# EvalBoard.net
KiCad netlist of a schematic drawn in EAGLE
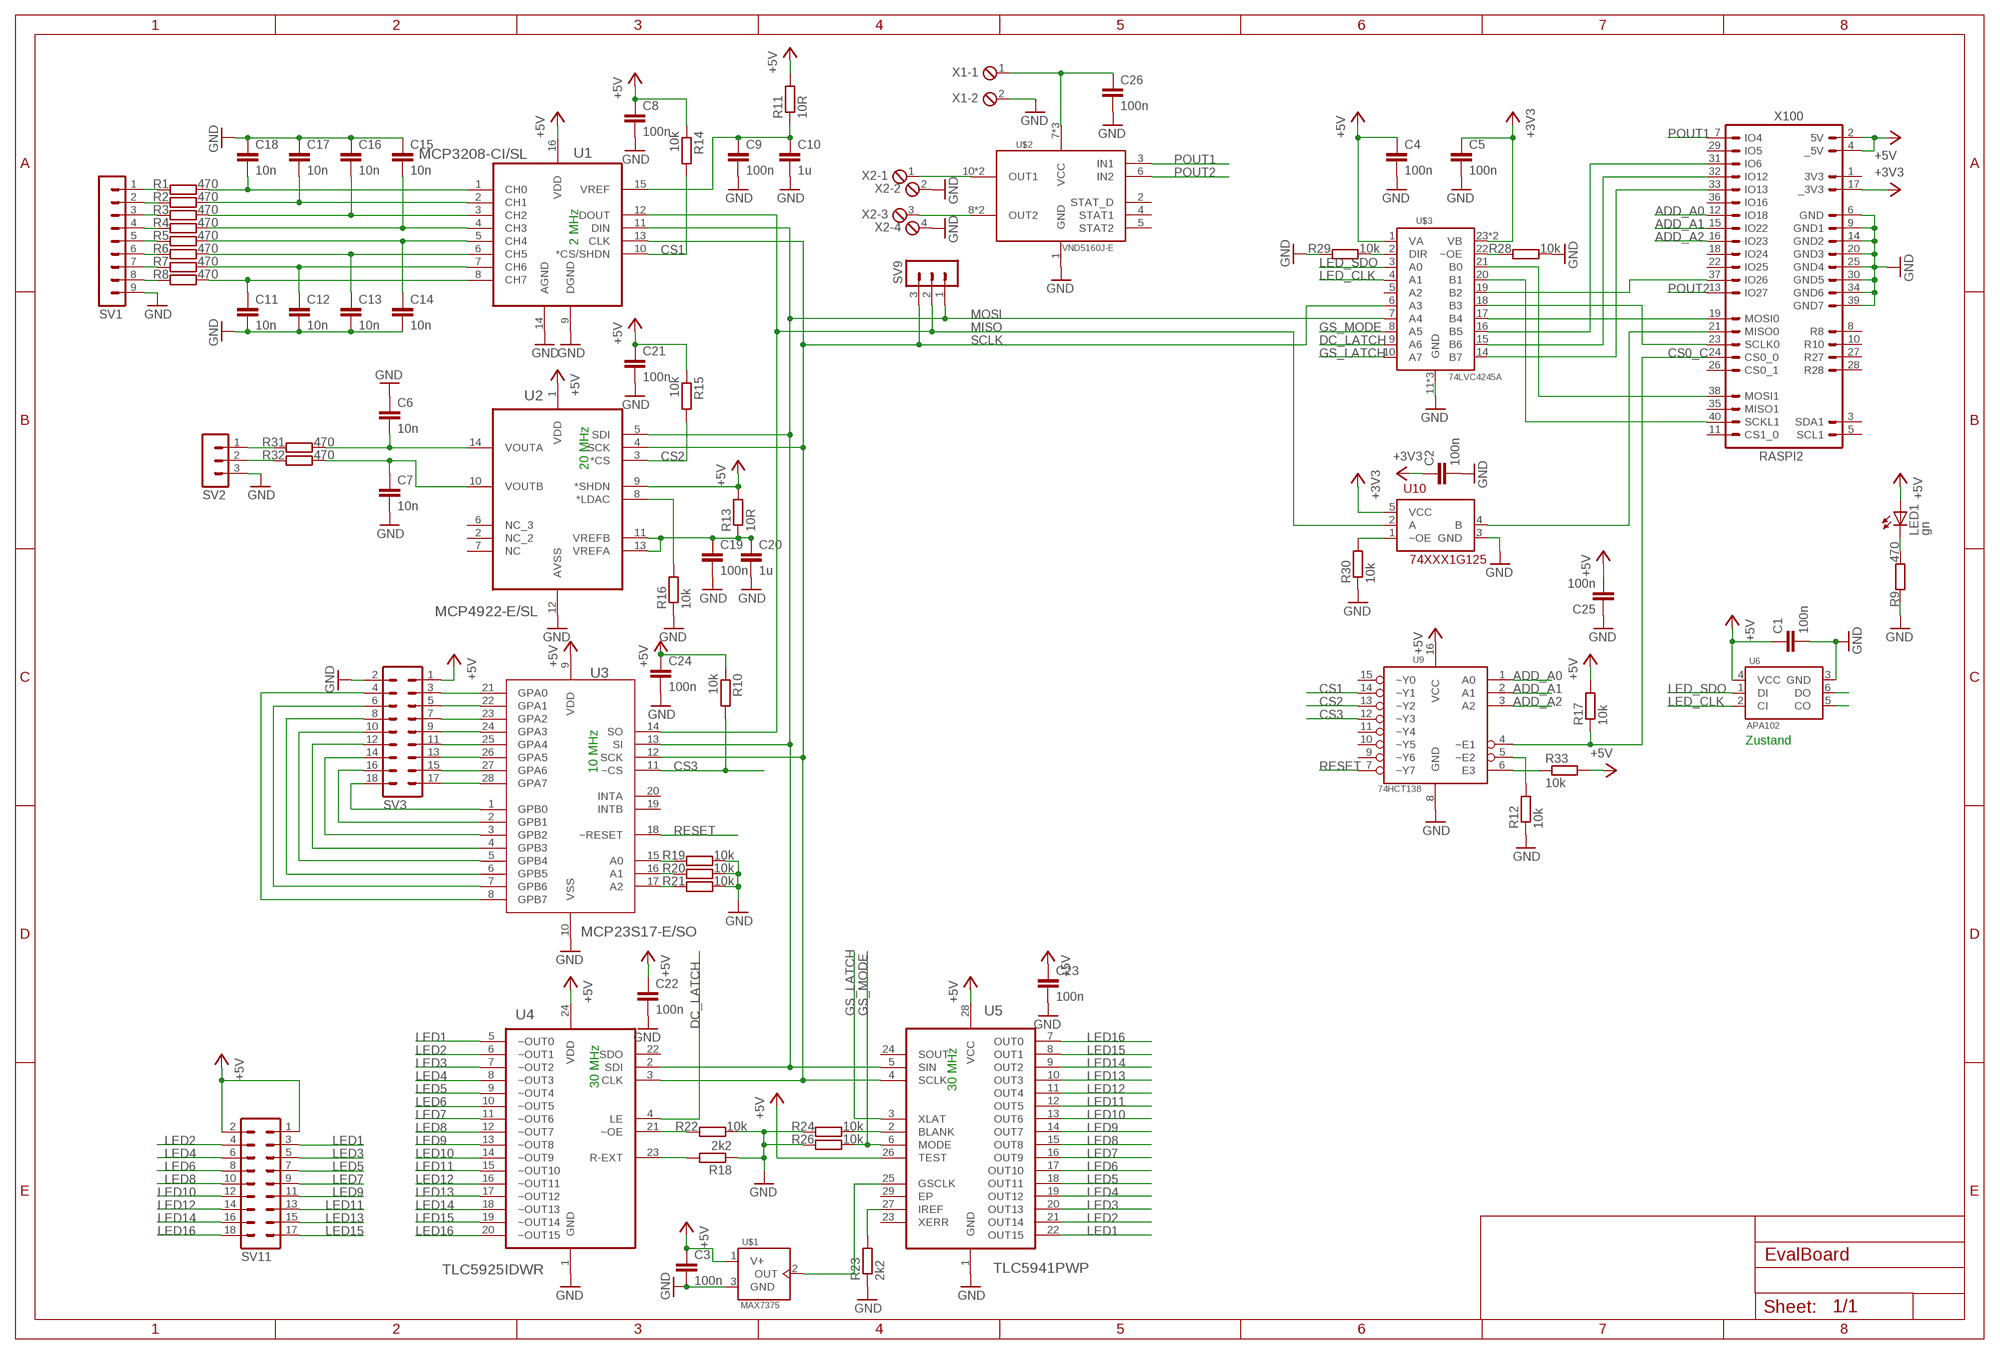
[diagram p0: schematic, sheet 1]

(export (version "E")
  (design (tool "Eeschema 10.0.6"))
  (components
    (comp (ref "C1")
      (value "100n")
      (footprint "eagle-import:C0805")
      (libsource (lib "eagle-import") (part "C-EUC0805"))
    )
    (comp (ref "C2")
      (value "100n")
      (footprint "eagle-import:C0805")
      (libsource (lib "eagle-import") (part "C-EUC0805"))
    )
    (comp (ref "C3")
      (value "100n")
      (footprint "eagle-import:C0805")
      (libsource (lib "eagle-import") (part "C-EUC0805"))
    )
    (comp (ref "C4")
      (value "100n")
      (footprint "eagle-import:C0805")
      (libsource (lib "eagle-import") (part "C-EUC0805"))
    )
    (comp (ref "C5")
      (value "100n")
      (footprint "eagle-import:C0805")
      (libsource (lib "eagle-import") (part "C-EUC0805"))
    )
    (comp (ref "C6")
      (value "10n")
      (footprint "eagle-import:C0805")
      (libsource (lib "eagle-import") (part "C-EUC0805"))
    )
    (comp (ref "C7")
      (value "10n")
      (footprint "eagle-import:C0805")
      (libsource (lib "eagle-import") (part "C-EUC0805"))
    )
    (comp (ref "C8")
      (value "100n")
      (footprint "eagle-import:C0805")
      (libsource (lib "eagle-import") (part "C-EUC0805"))
    )
    (comp (ref "C9")
      (value "100n")
      (footprint "eagle-import:C0805")
      (libsource (lib "eagle-import") (part "C-EUC0805"))
    )
    (comp (ref "C10")
      (value "1u")
      (footprint "eagle-import:C0805")
      (libsource (lib "eagle-import") (part "C-EUC0805"))
    )
    (comp (ref "C11")
      (value "10n")
      (footprint "eagle-import:C0805")
      (libsource (lib "eagle-import") (part "C-EUC0805"))
    )
    (comp (ref "C12")
      (value "10n")
      (footprint "eagle-import:C0805")
      (libsource (lib "eagle-import") (part "C-EUC0805"))
    )
    (comp (ref "C13")
      (value "10n")
      (footprint "eagle-import:C0805")
      (libsource (lib "eagle-import") (part "C-EUC0805"))
    )
    (comp (ref "C14")
      (value "10n")
      (footprint "eagle-import:C0805")
      (libsource (lib "eagle-import") (part "C-EUC0805"))
    )
    (comp (ref "C15")
      (value "10n")
      (footprint "eagle-import:C0805")
      (libsource (lib "eagle-import") (part "C-EUC0805"))
    )
    (comp (ref "C16")
      (value "10n")
      (footprint "eagle-import:C0805")
      (libsource (lib "eagle-import") (part "C-EUC0805"))
    )
    (comp (ref "C17")
      (value "10n")
      (footprint "eagle-import:C0805")
      (libsource (lib "eagle-import") (part "C-EUC0805"))
    )
    (comp (ref "C18")
      (value "10n")
      (footprint "eagle-import:C0805")
      (libsource (lib "eagle-import") (part "C-EUC0805"))
    )
    (comp (ref "C19")
      (value "100n")
      (footprint "eagle-import:C0805")
      (libsource (lib "eagle-import") (part "C-EUC0805"))
    )
    (comp (ref "C20")
      (value "1u")
      (footprint "eagle-import:C0805")
      (libsource (lib "eagle-import") (part "C-EUC0805"))
    )
    (comp (ref "C21")
      (value "100n")
      (footprint "eagle-import:C0805")
      (libsource (lib "eagle-import") (part "C-EUC0805"))
    )
    (comp (ref "C22")
      (value "100n")
      (footprint "eagle-import:C0805")
      (libsource (lib "eagle-import") (part "C-EUC0805"))
    )
    (comp (ref "C23")
      (value "100n")
      (footprint "eagle-import:C0805")
      (libsource (lib "eagle-import") (part "C-EUC0805"))
    )
    (comp (ref "C24")
      (value "100n")
      (footprint "eagle-import:C0805")
      (libsource (lib "eagle-import") (part "C-EUC0805"))
    )
    (comp (ref "C25")
      (value "100n")
      (footprint "eagle-import:C0805")
      (libsource (lib "eagle-import") (part "C-EUC0805"))
    )
    (comp (ref "C26")
      (value "100n")
      (footprint "eagle-import:C0805")
      (libsource (lib "eagle-import") (part "C-EUC0805"))
    )
    (comp (ref "LED1")
      (value "gn")
      (footprint "eagle-import:LED5MM")
      (libsource (lib "eagle-import") (part "LED5MM"))
    )
    (comp (ref "R1")
      (value "470")
      (footprint "eagle-import:R0805")
      (libsource (lib "eagle-import") (part "R-EU_R0805"))
    )
    (comp (ref "R2")
      (value "470")
      (footprint "eagle-import:R0805")
      (libsource (lib "eagle-import") (part "R-EU_R0805"))
    )
    (comp (ref "R3")
      (value "470")
      (footprint "eagle-import:R0805")
      (libsource (lib "eagle-import") (part "R-EU_R0805"))
    )
    (comp (ref "R4")
      (value "470")
      (footprint "eagle-import:R0805")
      (libsource (lib "eagle-import") (part "R-EU_R0805"))
    )
    (comp (ref "R5")
      (value "470")
      (footprint "eagle-import:R0805")
      (libsource (lib "eagle-import") (part "R-EU_R0805"))
    )
    (comp (ref "R6")
      (value "470")
      (footprint "eagle-import:R0805")
      (libsource (lib "eagle-import") (part "R-EU_R0805"))
    )
    (comp (ref "R7")
      (value "470")
      (footprint "eagle-import:R0805")
      (libsource (lib "eagle-import") (part "R-EU_R0805"))
    )
    (comp (ref "R8")
      (value "470")
      (footprint "eagle-import:R0805")
      (libsource (lib "eagle-import") (part "R-EU_R0805"))
    )
    (comp (ref "R9")
      (value "470")
      (footprint "eagle-import:R0805")
      (libsource (lib "eagle-import") (part "R-EU_R0805"))
    )
    (comp (ref "R10")
      (value "10k")
      (footprint "eagle-import:R0805")
      (libsource (lib "eagle-import") (part "R-EU_R0805"))
    )
    (comp (ref "R11")
      (value "10R")
      (footprint "eagle-import:R0805")
      (libsource (lib "eagle-import") (part "R-EU_R0805"))
    )
    (comp (ref "R12")
      (value "10k")
      (footprint "eagle-import:R0805")
      (libsource (lib "eagle-import") (part "R-EU_R0805"))
    )
    (comp (ref "R13")
      (value "10R")
      (footprint "eagle-import:R0805")
      (libsource (lib "eagle-import") (part "R-EU_R0805"))
    )
    (comp (ref "R14")
      (value "10k")
      (footprint "eagle-import:R0805")
      (libsource (lib "eagle-import") (part "R-EU_R0805"))
    )
    (comp (ref "R15")
      (value "10k")
      (footprint "eagle-import:R0805")
      (libsource (lib "eagle-import") (part "R-EU_R0805"))
    )
    (comp (ref "R16")
      (value "10k")
      (footprint "eagle-import:R0805")
      (libsource (lib "eagle-import") (part "R-EU_R0805"))
    )
    (comp (ref "R17")
      (value "10k")
      (footprint "eagle-import:R0805")
      (libsource (lib "eagle-import") (part "R-EU_R0805"))
    )
    (comp (ref "R18")
      (value "2k2")
      (footprint "eagle-import:R0805")
      (libsource (lib "eagle-import") (part "R-EU_R0805"))
    )
    (comp (ref "R19")
      (value "10k")
      (footprint "eagle-import:R0805")
      (libsource (lib "eagle-import") (part "R-EU_R0805"))
    )
    (comp (ref "R20")
      (value "10k")
      (footprint "eagle-import:R0805")
      (libsource (lib "eagle-import") (part "R-EU_R0805"))
    )
    (comp (ref "R21")
      (value "10k")
      (footprint "eagle-import:R0805")
      (libsource (lib "eagle-import") (part "R-EU_R0805"))
    )
    (comp (ref "R22")
      (value "10k")
      (footprint "eagle-import:R0805")
      (libsource (lib "eagle-import") (part "R-EU_R0805"))
    )
    (comp (ref "R23")
      (value "2k2")
      (footprint "eagle-import:R0805")
      (libsource (lib "eagle-import") (part "R-EU_R0805"))
    )
    (comp (ref "R24")
      (value "10k")
      (footprint "eagle-import:R0805")
      (libsource (lib "eagle-import") (part "R-EU_R0805"))
    )
    (comp (ref "R26")
      (value "10k")
      (footprint "eagle-import:R0805")
      (libsource (lib "eagle-import") (part "R-EU_R0805"))
    )
    (comp (ref "R28")
      (value "10k")
      (footprint "eagle-import:R0805")
      (libsource (lib "eagle-import") (part "R-EU_R0805"))
    )
    (comp (ref "R29")
      (value "10k")
      (footprint "eagle-import:R0805")
      (libsource (lib "eagle-import") (part "R-EU_R0805"))
    )
    (comp (ref "R30")
      (value "10k")
      (footprint "eagle-import:R0805")
      (libsource (lib "eagle-import") (part "R-EU_R0805"))
    )
    (comp (ref "R31")
      (value "470")
      (footprint "eagle-import:R0805")
      (libsource (lib "eagle-import") (part "R-EU_R0805"))
    )
    (comp (ref "R32")
      (value "470")
      (footprint "eagle-import:R0805")
      (libsource (lib "eagle-import") (part "R-EU_R0805"))
    )
    (comp (ref "R33")
      (value "10k")
      (footprint "eagle-import:R0805")
      (libsource (lib "eagle-import") (part "R-EU_R0805"))
    )
    (comp (ref "SV1")
      (value "MA09-1W")
      (footprint "eagle-import:MA09-1W")
      (libsource (lib "eagle-import") (part "MA09-1W"))
    )
    (comp (ref "SV2")
      (value "MA03-1")
      (footprint "eagle-import:MA03-1")
      (libsource (lib "eagle-import") (part "MA03-1"))
    )
    (comp (ref "SV3")
      (value "MA09-2W")
      (footprint "eagle-import:MA09-2W")
      (libsource (lib "eagle-import") (part "MA09-2W"))
    )
    (comp (ref "SV9")
      (value "MA03-1")
      (footprint "eagle-import:MA03-1")
      (libsource (lib "eagle-import") (part "MA03-1"))
    )
    (comp (ref "SV11")
      (value "MA09-2W")
      (footprint "eagle-import:MA09-2W")
      (libsource (lib "eagle-import") (part "MA09-2W"))
    )
    (comp (ref "U$1")
      (value "MAX7375")
      (footprint "eagle-import:SC70")
      (libsource (lib "eagle-import") (part "MAX7375"))
    )
    (comp (ref "U$2")
      (value "VND5160J-E")
      (footprint "eagle-import:POWERSSO12")
      (libsource (lib "eagle-import") (part "VND5160J-E"))
    )
    (comp (ref "U$3")
      (value "74LVC4245A")
      (footprint "eagle-import:SOIC127P1030X265-24N")
      (libsource (lib "eagle-import") (part "74LVC4245A"))
    )
    (comp (ref "U1")
      (value "MCP3208-CI/SL")
      (footprint "eagle-import:SOIC127P600X175-16N")
      (libsource (lib "eagle-import") (part "MCP3208-CI/SL"))
    )
    (comp (ref "U2")
      (value "MCP4922-E/SL")
      (footprint "eagle-import:SOIC127P600X175-14N")
      (libsource (lib "eagle-import") (part "MCP4922-E/SL"))
    )
    (comp (ref "U3")
      (value "MCP23S17-E/SO")
      (footprint "eagle-import:SOIC127P030X265-28N")
      (libsource (lib "eagle-import") (part "MCP23S17-E/SO"))
    )
    (comp (ref "U4")
      (value "TLC5925IDWR")
      (footprint "eagle-import:SOIC127P1030X265-24N")
      (libsource (lib "eagle-import") (part "TLC5925IDWR"))
    )
    (comp (ref "U5")
      (value "TLC5941PWP")
      (footprint "eagle-import:SOP65P640X120-29N")
      (libsource (lib "eagle-import") (part "TLC5941PWP"))
    )
    (comp (ref "U6")
      (value "APA102")
      (footprint "eagle-import:LED5050PACK")
      (libsource (lib "eagle-import") (part "APA102"))
    )
    (comp (ref "U9")
      (value "74HCT138")
      (footprint "eagle-import:SOIC127P600X175-16N")
      (libsource (lib "eagle-import") (part "74HCT138"))
    )
    (comp (ref "U10")
      (value "74XXX1G125")
      (footprint "eagle-import:SOT23-5L")
      (libsource (lib "eagle-import") (part "74XXX1G125"))
    )
    (comp (ref "X1")
      (value "MPT2")
      (footprint "eagle-import:2POL254")
      (libsource (lib "eagle-import") (part "MPT2"))
    )
    (comp (ref "X2")
      (value "MPT4")
      (footprint "eagle-import:4POL254")
      (libsource (lib "eagle-import") (part "MPT4"))
    )
    (comp (ref "X100")
      (value "RASPI2")
      (footprint "eagle-import:ML40")
      (libsource (lib "eagle-import") (part "RASPI2"))
    )
  )
  (nets
    (net (code "1") (name "+3V3") (class "Default")
      (node (ref "C2") (pin "1") (pinfunction "1_1") (pintype "passive"))
      (node (ref "C5") (pin "1") (pinfunction "1_1") (pintype "passive"))
      (node (ref "U$3") (pin "23") (pinfunction "VB_23") (pintype "power_in"))
      (node (ref "U$3") (pin "24") (pinfunction "VB_24") (pintype "power_in"))
      (node (ref "U10") (pin "5") (pinfunction "VCC_5") (pintype "bidirectional"))
      (node (ref "X100") (pin "17") (pinfunction "_3V3_17") (pintype "passive"))
    )
    (net (code "2") (name "+5V") (class "Default")
      (node (ref "C1") (pin "1") (pinfunction "1_1") (pintype "passive"))
      (node (ref "C21") (pin "1") (pinfunction "1_1") (pintype "passive"))
      (node (ref "C22") (pin "1") (pinfunction "1_1") (pintype "passive"))
      (node (ref "C23") (pin "1") (pinfunction "1_1") (pintype "passive"))
      (node (ref "C24") (pin "1") (pinfunction "1_1") (pintype "passive"))
      (node (ref "C25") (pin "2") (pinfunction "2_2") (pintype "passive"))
      (node (ref "C3") (pin "1") (pinfunction "1_1") (pintype "passive"))
      (node (ref "C4") (pin "1") (pinfunction "1_1") (pintype "passive"))
      (node (ref "C8") (pin "1") (pinfunction "1_1") (pintype "passive"))
      (node (ref "LED1") (pin "A") (pinfunction "A_A") (pintype "passive"))
      (node (ref "R10") (pin "1") (pinfunction "1_1") (pintype "passive"))
      (node (ref "R11") (pin "2") (pinfunction "2_2") (pintype "passive"))
      (node (ref "R13") (pin "2") (pinfunction "2_2") (pintype "passive"))
      (node (ref "R14") (pin "1") (pinfunction "1_1") (pintype "passive"))
      (node (ref "R15") (pin "1") (pinfunction "1_1") (pintype "passive"))
      (node (ref "R17") (pin "2") (pinfunction "2_2") (pintype "passive"))
      (node (ref "R33") (pin "2") (pinfunction "2_2") (pintype "passive"))
      (node (ref "SV11") (pin "1") (pinfunction "1_1") (pintype "passive"))
      (node (ref "SV11") (pin "2") (pinfunction "2_2") (pintype "passive"))
      (node (ref "SV3") (pin "1") (pinfunction "1_1") (pintype "passive"))
      (node (ref "U$1") (pin "1") (pinfunction "V+_1") (pintype "power_in"))
      (node (ref "U$3") (pin "1") (pinfunction "VA_1") (pintype "power_in"))
      (node (ref "U1") (pin "16") (pinfunction "VDD_16") (pintype "power_in"))
      (node (ref "U2") (pin "1") (pinfunction "VDD_1") (pintype "power_in"))
      (node (ref "U2") (pin "9") (pinfunction "*SHDN_9") (pintype "input"))
      (node (ref "U3") (pin "9") (pinfunction "VDD_9") (pintype "power_in"))
      (node (ref "U4") (pin "24") (pinfunction "VDD_24") (pintype "power_in"))
      (node (ref "U5") (pin "26") (pinfunction "TEST_26") (pintype "input"))
      (node (ref "U5") (pin "28") (pinfunction "VCC_28") (pintype "power_in"))
      (node (ref "U6") (pin "4") (pinfunction "VCC_4") (pintype "bidirectional"))
      (node (ref "U9") (pin "16") (pinfunction "VCC_16") (pintype "bidirectional"))
      (node (ref "X100") (pin "2") (pinfunction "5V_2") (pintype "passive"))
      (node (ref "X100") (pin "4") (pinfunction "_5V_4") (pintype "passive"))
    )
    (net (code "3") (name "/ADD_A0") (class "Default")
      (node (ref "U9") (pin "1") (pinfunction "A0_1") (pintype "bidirectional"))
      (node (ref "X100") (pin "12") (pinfunction "IO18_12") (pintype "passive"))
    )
    (net (code "4") (name "/ADD_A1") (class "Default")
      (node (ref "U9") (pin "2") (pinfunction "A1_2") (pintype "bidirectional"))
      (node (ref "X100") (pin "15") (pinfunction "IO22_15") (pintype "passive"))
    )
    (net (code "5") (name "/ADD_A2") (class "Default")
      (node (ref "U9") (pin "3") (pinfunction "A2_3") (pintype "bidirectional"))
      (node (ref "X100") (pin "16") (pinfunction "IO23_16") (pintype "passive"))
    )
    (net (code "6") (name "/CS0_C") (class "Default")
      (node (ref "R17") (pin "1") (pinfunction "1_1") (pintype "passive"))
      (node (ref "U9") (pin "4") (pinfunction "~{E1}_4") (pintype "bidirectional"))
      (node (ref "X100") (pin "24") (pinfunction "CS0_0_24") (pintype "passive"))
    )
    (net (code "7") (name "/CS1") (class "Default")
      (node (ref "R14") (pin "2") (pinfunction "2_2") (pintype "passive"))
      (node (ref "U1") (pin "10") (pinfunction "*CS/SHDN_10") (pintype "input"))
      (node (ref "U9") (pin "14") (pinfunction "~{Y1}_14") (pintype "bidirectional"))
    )
    (net (code "8") (name "/CS2") (class "Default")
      (node (ref "R15") (pin "2") (pinfunction "2_2") (pintype "passive"))
      (node (ref "U2") (pin "3") (pinfunction "*CS_3") (pintype "input"))
      (node (ref "U9") (pin "13") (pinfunction "~{Y2}_13") (pintype "bidirectional"))
    )
    (net (code "9") (name "/CS3") (class "Default")
      (node (ref "R10") (pin "2") (pinfunction "2_2") (pintype "passive"))
      (node (ref "U3") (pin "11") (pinfunction "~{CS}_11") (pintype "input"))
      (node (ref "U9") (pin "12") (pinfunction "~{Y3}_12") (pintype "bidirectional"))
    )
    (net (code "10") (name "/DC_LATCH") (class "Default")
      (node (ref "U$3") (pin "9") (pinfunction "A6_9") (pintype "bidirectional"))
      (node (ref "U4") (pin "4") (pinfunction "LE_4") (pintype "input"))
    )
    (net (code "11") (name "/GS_LATCH") (class "Default")
      (node (ref "U$3") (pin "10") (pinfunction "A7_10") (pintype "bidirectional"))
      (node (ref "U5") (pin "3") (pinfunction "XLAT_3") (pintype "input"))
    )
    (net (code "12") (name "/GS_MODE") (class "Default")
      (node (ref "R26") (pin "2") (pinfunction "2_2") (pintype "passive"))
      (node (ref "U$3") (pin "8") (pinfunction "A5_8") (pintype "bidirectional"))
      (node (ref "U5") (pin "6") (pinfunction "MODE_6") (pintype "input"))
    )
    (net (code "13") (name "/LED1") (class "Default")
      (node (ref "SV11") (pin "3") (pinfunction "3_3") (pintype "passive"))
      (node (ref "U4") (pin "5") (pinfunction "~{OUT0}_5") (pintype "output"))
      (node (ref "U5") (pin "22") (pinfunction "OUT15_22") (pintype "output"))
    )
    (net (code "14") (name "/LED2") (class "Default")
      (node (ref "SV11") (pin "4") (pinfunction "4_4") (pintype "passive"))
      (node (ref "U4") (pin "6") (pinfunction "~{OUT1}_6") (pintype "output"))
      (node (ref "U5") (pin "21") (pinfunction "OUT14_21") (pintype "output"))
    )
    (net (code "15") (name "/LED3") (class "Default")
      (node (ref "SV11") (pin "5") (pinfunction "5_5") (pintype "passive"))
      (node (ref "U4") (pin "7") (pinfunction "~{OUT2}_7") (pintype "output"))
      (node (ref "U5") (pin "20") (pinfunction "OUT13_20") (pintype "output"))
    )
    (net (code "16") (name "/LED4") (class "Default")
      (node (ref "SV11") (pin "6") (pinfunction "6_6") (pintype "passive"))
      (node (ref "U4") (pin "8") (pinfunction "~{OUT3}_8") (pintype "output"))
      (node (ref "U5") (pin "19") (pinfunction "OUT12_19") (pintype "output"))
    )
    (net (code "17") (name "/LED5") (class "Default")
      (node (ref "SV11") (pin "7") (pinfunction "7_7") (pintype "passive"))
      (node (ref "U4") (pin "9") (pinfunction "~{OUT4}_9") (pintype "output"))
      (node (ref "U5") (pin "18") (pinfunction "OUT11_18") (pintype "output"))
    )
    (net (code "18") (name "/LED6") (class "Default")
      (node (ref "SV11") (pin "8") (pinfunction "8_8") (pintype "passive"))
      (node (ref "U4") (pin "10") (pinfunction "~{OUT5}_10") (pintype "output"))
      (node (ref "U5") (pin "17") (pinfunction "OUT10_17") (pintype "output"))
    )
    (net (code "19") (name "/LED7") (class "Default")
      (node (ref "SV11") (pin "9") (pinfunction "9_9") (pintype "passive"))
      (node (ref "U4") (pin "11") (pinfunction "~{OUT6}_11") (pintype "output"))
      (node (ref "U5") (pin "16") (pinfunction "OUT9_16") (pintype "output"))
    )
    (net (code "20") (name "/LED8") (class "Default")
      (node (ref "SV11") (pin "10") (pinfunction "10_10") (pintype "passive"))
      (node (ref "U4") (pin "12") (pinfunction "~{OUT7}_12") (pintype "output"))
      (node (ref "U5") (pin "15") (pinfunction "OUT8_15") (pintype "output"))
    )
    (net (code "21") (name "/LED9") (class "Default")
      (node (ref "SV11") (pin "11") (pinfunction "11_11") (pintype "passive"))
      (node (ref "U4") (pin "13") (pinfunction "~{OUT8}_13") (pintype "output"))
      (node (ref "U5") (pin "14") (pinfunction "OUT7_14") (pintype "output"))
    )
    (net (code "22") (name "/LED10") (class "Default")
      (node (ref "SV11") (pin "12") (pinfunction "12_12") (pintype "passive"))
      (node (ref "U4") (pin "14") (pinfunction "~{OUT9}_14") (pintype "output"))
      (node (ref "U5") (pin "13") (pinfunction "OUT6_13") (pintype "output"))
    )
    (net (code "23") (name "/LED11") (class "Default")
      (node (ref "SV11") (pin "13") (pinfunction "13_13") (pintype "passive"))
      (node (ref "U4") (pin "15") (pinfunction "~{OUT10}_15") (pintype "output"))
      (node (ref "U5") (pin "12") (pinfunction "OUT5_12") (pintype "output"))
    )
    (net (code "24") (name "/LED12") (class "Default")
      (node (ref "SV11") (pin "14") (pinfunction "14_14") (pintype "passive"))
      (node (ref "U4") (pin "16") (pinfunction "~{OUT11}_16") (pintype "output"))
      (node (ref "U5") (pin "11") (pinfunction "OUT4_11") (pintype "output"))
    )
    (net (code "25") (name "/LED13") (class "Default")
      (node (ref "SV11") (pin "15") (pinfunction "15_15") (pintype "passive"))
      (node (ref "U4") (pin "17") (pinfunction "~{OUT12}_17") (pintype "output"))
      (node (ref "U5") (pin "10") (pinfunction "OUT3_10") (pintype "output"))
    )
    (net (code "26") (name "/LED14") (class "Default")
      (node (ref "SV11") (pin "16") (pinfunction "16_16") (pintype "passive"))
      (node (ref "U4") (pin "18") (pinfunction "~{OUT13}_18") (pintype "output"))
      (node (ref "U5") (pin "9") (pinfunction "OUT2_9") (pintype "output"))
    )
    (net (code "27") (name "/LED15") (class "Default")
      (node (ref "SV11") (pin "17") (pinfunction "17_17") (pintype "passive"))
      (node (ref "U4") (pin "19") (pinfunction "~{OUT14}_19") (pintype "output"))
      (node (ref "U5") (pin "8") (pinfunction "OUT1_8") (pintype "output"))
    )
    (net (code "28") (name "/LED16") (class "Default")
      (node (ref "SV11") (pin "18") (pinfunction "18_18") (pintype "passive"))
      (node (ref "U4") (pin "20") (pinfunction "~{OUT15}_20") (pintype "output"))
      (node (ref "U5") (pin "7") (pinfunction "OUT0_7") (pintype "output"))
    )
    (net (code "29") (name "/LED_CLK") (class "Default")
      (node (ref "U$3") (pin "4") (pinfunction "A1_4") (pintype "bidirectional"))
      (node (ref "U6") (pin "2") (pinfunction "CI_2") (pintype "bidirectional"))
    )
    (net (code "30") (name "/LED_SDO") (class "Default")
      (node (ref "U$3") (pin "3") (pinfunction "A0_3") (pintype "bidirectional"))
      (node (ref "U6") (pin "1") (pinfunction "DI_1") (pintype "bidirectional"))
    )
    (net (code "31") (name "/MISO") (class "Default")
      (node (ref "SV9") (pin "2") (pinfunction "2_2") (pintype "passive"))
      (node (ref "U1") (pin "12") (pinfunction "DOUT_12") (pintype "output"))
      (node (ref "U10") (pin "2") (pinfunction "A_2") (pintype "bidirectional"))
      (node (ref "U3") (pin "14") (pinfunction "SO_14") (pintype "output"))
    )
    (net (code "32") (name "/MOSI") (class "Default")
      (node (ref "SV9") (pin "1") (pinfunction "1_1") (pintype "passive"))
      (node (ref "U$3") (pin "7") (pinfunction "A4_7") (pintype "bidirectional"))
      (node (ref "U1") (pin "11") (pinfunction "DIN_11") (pintype "input"))
      (node (ref "U2") (pin "5") (pinfunction "SDI_5") (pintype "input"))
      (node (ref "U3") (pin "13") (pinfunction "SI_13") (pintype "input"))
      (node (ref "U4") (pin "2") (pinfunction "SDI_2") (pintype "input"))
      (node (ref "U5") (pin "5") (pinfunction "SIN_5") (pintype "input"))
    )
    (net (code "33") (name "/POUT1") (class "Default")
      (node (ref "U$2") (pin "3") (pinfunction "IN1_3") (pintype "input"))
      (node (ref "X100") (pin "7") (pinfunction "IO4_7") (pintype "passive"))
    )
    (net (code "34") (name "/POUT2") (class "Default")
      (node (ref "U$2") (pin "6") (pinfunction "IN2_6") (pintype "input"))
      (node (ref "X100") (pin "13") (pinfunction "IO27_13") (pintype "passive"))
    )
    (net (code "35") (name "/RESET") (class "Default")
      (node (ref "U3") (pin "18") (pinfunction "~{RESET}_18") (pintype "input"))
      (node (ref "U9") (pin "7") (pinfunction "~{Y7}_7") (pintype "bidirectional"))
    )
    (net (code "36") (name "/SCLK") (class "Default")
      (node (ref "SV9") (pin "3") (pinfunction "3_3") (pintype "passive"))
      (node (ref "U$3") (pin "6") (pinfunction "A3_6") (pintype "bidirectional"))
      (node (ref "U1") (pin "13") (pinfunction "CLK_13") (pintype "input"))
      (node (ref "U2") (pin "4") (pinfunction "SCK_4") (pintype "input"))
      (node (ref "U3") (pin "12") (pinfunction "SCK_12") (pintype "input"))
      (node (ref "U4") (pin "3") (pinfunction "CLK_3") (pintype "input"))
      (node (ref "U5") (pin "4") (pinfunction "SCLK_4") (pintype "input"))
    )
    (net (code "37") (name "GND") (class "Default")
      (node (ref "C1") (pin "2") (pinfunction "2_2") (pintype "passive"))
      (node (ref "C10") (pin "2") (pinfunction "2_2") (pintype "passive"))
      (node (ref "C11") (pin "2") (pinfunction "2_2") (pintype "passive"))
      (node (ref "C12") (pin "2") (pinfunction "2_2") (pintype "passive"))
      (node (ref "C13") (pin "2") (pinfunction "2_2") (pintype "passive"))
      (node (ref "C14") (pin "2") (pinfunction "2_2") (pintype "passive"))
      (node (ref "C15") (pin "1") (pinfunction "1_1") (pintype "passive"))
      (node (ref "C16") (pin "1") (pinfunction "1_1") (pintype "passive"))
      (node (ref "C17") (pin "1") (pinfunction "1_1") (pintype "passive"))
      (node (ref "C18") (pin "1") (pinfunction "1_1") (pintype "passive"))
      (node (ref "C19") (pin "2") (pinfunction "2_2") (pintype "passive"))
      (node (ref "C2") (pin "2") (pinfunction "2_2") (pintype "passive"))
      (node (ref "C20") (pin "2") (pinfunction "2_2") (pintype "passive"))
      (node (ref "C21") (pin "2") (pinfunction "2_2") (pintype "passive"))
      (node (ref "C22") (pin "2") (pinfunction "2_2") (pintype "passive"))
      (node (ref "C23") (pin "2") (pinfunction "2_2") (pintype "passive"))
      (node (ref "C24") (pin "2") (pinfunction "2_2") (pintype "passive"))
      (node (ref "C25") (pin "1") (pinfunction "1_1") (pintype "passive"))
      (node (ref "C26") (pin "2") (pinfunction "2_2") (pintype "passive"))
      (node (ref "C3") (pin "2") (pinfunction "2_2") (pintype "passive"))
      (node (ref "C4") (pin "2") (pinfunction "2_2") (pintype "passive"))
      (node (ref "C5") (pin "2") (pinfunction "2_2") (pintype "passive"))
      (node (ref "C6") (pin "1") (pinfunction "1_1") (pintype "passive"))
      (node (ref "C7") (pin "2") (pinfunction "2_2") (pintype "passive"))
      (node (ref "C8") (pin "2") (pinfunction "2_2") (pintype "passive"))
      (node (ref "C9") (pin "2") (pinfunction "2_2") (pintype "passive"))
      (node (ref "R12") (pin "1") (pinfunction "1_1") (pintype "passive"))
      (node (ref "R16") (pin "1") (pinfunction "1_1") (pintype "passive"))
      (node (ref "R18") (pin "1") (pinfunction "1_1") (pintype "passive"))
      (node (ref "R19") (pin "2") (pinfunction "2_2") (pintype "passive"))
      (node (ref "R20") (pin "2") (pinfunction "2_2") (pintype "passive"))
      (node (ref "R21") (pin "2") (pinfunction "2_2") (pintype "passive"))
      (node (ref "R22") (pin "2") (pinfunction "2_2") (pintype "passive"))
      (node (ref "R23") (pin "1") (pinfunction "1_1") (pintype "passive"))
      (node (ref "R24") (pin "1") (pinfunction "1_1") (pintype "passive"))
      (node (ref "R26") (pin "1") (pinfunction "1_1") (pintype "passive"))
      (node (ref "R28") (pin "2") (pinfunction "2_2") (pintype "passive"))
      (node (ref "R29") (pin "1") (pinfunction "1_1") (pintype "passive"))
      (node (ref "R30") (pin "1") (pinfunction "1_1") (pintype "passive"))
      (node (ref "R9") (pin "1") (pinfunction "1_1") (pintype "passive"))
      (node (ref "SV1") (pin "9") (pinfunction "9_9") (pintype "passive"))
      (node (ref "SV2") (pin "3") (pinfunction "3_3") (pintype "passive"))
      (node (ref "SV3") (pin "2") (pinfunction "2_2") (pintype "passive"))
      (node (ref "U$1") (pin "3") (pinfunction "GND_3") (pintype "power_in"))
      (node (ref "U$2") (pin "1") (pinfunction "GND_1") (pintype "power_in"))
      (node (ref "U$3") (pin "11") (pinfunction "GND_11") (pintype "power_in"))
      (node (ref "U$3") (pin "12") (pinfunction "GND_12") (pintype "power_in"))
      (node (ref "U$3") (pin "13") (pinfunction "GND_13") (pintype "power_in"))
      (node (ref "U1") (pin "14") (pinfunction "AGND_14") (pintype "passive"))
      (node (ref "U1") (pin "9") (pinfunction "DGND_9") (pintype "passive"))
      (node (ref "U10") (pin "3") (pinfunction "GND_3") (pintype "bidirectional"))
      (node (ref "U2") (pin "12") (pinfunction "AVSS_12") (pintype "passive"))
      (node (ref "U3") (pin "10") (pinfunction "VSS_10") (pintype "power_in"))
      (node (ref "U4") (pin "1") (pinfunction "GND_1") (pintype "passive"))
      (node (ref "U5") (pin "1") (pinfunction "GND_1") (pintype "passive"))
      (node (ref "U6") (pin "3") (pinfunction "GND_3") (pintype "bidirectional"))
      (node (ref "U9") (pin "8") (pinfunction "GND_8") (pintype "bidirectional"))
      (node (ref "X1") (pin "2") (pinfunction "1_2") (pintype "passive"))
      (node (ref "X100") (pin "14") (pinfunction "GND2_14") (pintype "passive"))
      (node (ref "X100") (pin "20") (pinfunction "GND3_20") (pintype "passive"))
      (node (ref "X100") (pin "25") (pinfunction "GND4_25") (pintype "passive"))
      (node (ref "X100") (pin "30") (pinfunction "GND5_30") (pintype "passive"))
      (node (ref "X100") (pin "34") (pinfunction "GND6_34") (pintype "passive"))
      (node (ref "X100") (pin "39") (pinfunction "GND7_39") (pintype "passive"))
      (node (ref "X100") (pin "6") (pinfunction "GND_6") (pintype "passive"))
      (node (ref "X100") (pin "9") (pinfunction "GND1_9") (pintype "passive"))
      (node (ref "X2") (pin "2") (pinfunction "1_2") (pintype "passive"))
      (node (ref "X2") (pin "4") (pinfunction "1_4") (pintype "passive"))
    )
    (net (code "38") (name "Net-(C26-Pad1)") (class "Default")
      (node (ref "C26") (pin "1") (pinfunction "1_1") (pintype "passive"))
      (node (ref "U$2") (pin "12") (pinfunction "VCC_12") (pintype "power_in"))
      (node (ref "U$2") (pin "7") (pinfunction "VCC_7") (pintype "power_in"))
      (node (ref "U$2") (pin "TP") (pinfunction "VCC_TP") (pintype "power_in"))
      (node (ref "X1") (pin "1") (pinfunction "1_1") (pintype "passive"))
    )
    (net (code "39") (name "Net-(LED1-C)") (class "Default")
      (node (ref "LED1") (pin "K") (pinfunction "C_K") (pintype "passive"))
      (node (ref "R9") (pin "2") (pinfunction "2_2") (pintype "passive"))
    )
    (net (code "40") (name "Net-(R1-Pad1)") (class "Default")
      (node (ref "R1") (pin "1") (pinfunction "1_1") (pintype "passive"))
      (node (ref "SV1") (pin "1") (pinfunction "1_1") (pintype "passive"))
    )
    (net (code "41") (name "Net-(R2-Pad1)") (class "Default")
      (node (ref "R2") (pin "1") (pinfunction "1_1") (pintype "passive"))
      (node (ref "SV1") (pin "2") (pinfunction "2_2") (pintype "passive"))
    )
    (net (code "42") (name "Net-(R3-Pad1)") (class "Default")
      (node (ref "R3") (pin "1") (pinfunction "1_1") (pintype "passive"))
      (node (ref "SV1") (pin "3") (pinfunction "3_3") (pintype "passive"))
    )
    (net (code "43") (name "Net-(R4-Pad1)") (class "Default")
      (node (ref "R4") (pin "1") (pinfunction "1_1") (pintype "passive"))
      (node (ref "SV1") (pin "4") (pinfunction "4_4") (pintype "passive"))
    )
    (net (code "44") (name "Net-(R5-Pad1)") (class "Default")
      (node (ref "R5") (pin "1") (pinfunction "1_1") (pintype "passive"))
      (node (ref "SV1") (pin "5") (pinfunction "5_5") (pintype "passive"))
    )
    (net (code "45") (name "Net-(R6-Pad1)") (class "Default")
      (node (ref "R6") (pin "1") (pinfunction "1_1") (pintype "passive"))
      (node (ref "SV1") (pin "6") (pinfunction "6_6") (pintype "passive"))
    )
    (net (code "46") (name "Net-(R7-Pad1)") (class "Default")
      (node (ref "R7") (pin "1") (pinfunction "1_1") (pintype "passive"))
      (node (ref "SV1") (pin "7") (pinfunction "7_7") (pintype "passive"))
    )
    (net (code "47") (name "Net-(R8-Pad1)") (class "Default")
      (node (ref "R8") (pin "1") (pinfunction "1_1") (pintype "passive"))
      (node (ref "SV1") (pin "8") (pinfunction "8_8") (pintype "passive"))
    )
    (net (code "48") (name "Net-(R31-Pad1)") (class "Default")
      (node (ref "R31") (pin "1") (pinfunction "1_1") (pintype "passive"))
      (node (ref "SV2") (pin "1") (pinfunction "1_1") (pintype "passive"))
    )
    (net (code "49") (name "Net-(R32-Pad1)") (class "Default")
      (node (ref "R32") (pin "1") (pinfunction "1_1") (pintype "passive"))
      (node (ref "SV2") (pin "2") (pinfunction "2_2") (pintype "passive"))
    )
    (net (code "50") (name "Net-(U$1-OUT)") (class "Default")
      (node (ref "U$1") (pin "2") (pinfunction "OUT_2") (pintype "output"))
      (node (ref "U5") (pin "25") (pinfunction "GSCLK_25") (pintype "output"))
    )
    (net (code "51") (name "Net-(U$2-OUT1-Pad10)") (class "Default")
      (node (ref "U$2") (pin "10") (pinfunction "OUT1_10") (pintype "output"))
      (node (ref "U$2") (pin "11") (pinfunction "OUT1_11") (pintype "output"))
      (node (ref "X2") (pin "1") (pinfunction "1_1") (pintype "passive"))
    )
    (net (code "52") (name "Net-(U$3-B0)") (class "Default")
      (node (ref "U$3") (pin "21") (pinfunction "B0_21") (pintype "bidirectional"))
      (node (ref "X100") (pin "38") (pinfunction "MOSI1_38") (pintype "passive"))
    )
    (net (code "53") (name "Net-(U$3-B1)") (class "Default")
      (node (ref "U$3") (pin "20") (pinfunction "B1_20") (pintype "bidirectional"))
      (node (ref "X100") (pin "40") (pinfunction "SCKL1_40") (pintype "passive"))
    )
    (net (code "54") (name "Net-(U$3-B2)") (class "Default")
      (node (ref "U$3") (pin "19") (pinfunction "B2_19") (pintype "bidirectional"))
      (node (ref "X100") (pin "37") (pinfunction "IO26_37") (pintype "passive"))
    )
    (net (code "55") (name "Net-(U$3-B3)") (class "Default")
      (node (ref "U$3") (pin "18") (pinfunction "B3_18") (pintype "bidirectional"))
      (node (ref "X100") (pin "23") (pinfunction "SCLK0_23") (pintype "passive"))
    )
    (net (code "56") (name "Net-(U$3-B4)") (class "Default")
      (node (ref "U$3") (pin "17") (pinfunction "B4_17") (pintype "bidirectional"))
      (node (ref "X100") (pin "19") (pinfunction "MOSI0_19") (pintype "passive"))
    )
    (net (code "57") (name "Net-(U$3-B5)") (class "Default")
      (node (ref "U$3") (pin "16") (pinfunction "B5_16") (pintype "bidirectional"))
      (node (ref "X100") (pin "31") (pinfunction "IO6_31") (pintype "passive"))
    )
    (net (code "58") (name "Net-(U$3-B6)") (class "Default")
      (node (ref "U$3") (pin "15") (pinfunction "B6_15") (pintype "bidirectional"))
      (node (ref "X100") (pin "32") (pinfunction "IO12_32") (pintype "passive"))
    )
    (net (code "59") (name "Net-(U$3-B7)") (class "Default")
      (node (ref "U$3") (pin "14") (pinfunction "B7_14") (pintype "bidirectional"))
      (node (ref "X100") (pin "33") (pinfunction "IO13_33") (pintype "passive"))
    )
    (net (code "60") (name "Net-(U$3-DIR)") (class "Default")
      (node (ref "R29") (pin "2") (pinfunction "2_2") (pintype "passive"))
      (node (ref "U$3") (pin "2") (pinfunction "DIR_2") (pintype "input"))
    )
    (net (code "61") (name "Net-(U$3-~{OE})") (class "Default")
      (node (ref "R28") (pin "1") (pinfunction "1_1") (pintype "passive"))
      (node (ref "U$3") (pin "22") (pinfunction "~{OE}_22") (pintype "input"))
    )
    (net (code "62") (name "Net-(U1-CH0)") (class "Default")
      (node (ref "C18") (pin "2") (pinfunction "2_2") (pintype "passive"))
      (node (ref "R1") (pin "2") (pinfunction "2_2") (pintype "passive"))
      (node (ref "U1") (pin "1") (pinfunction "CH0_1") (pintype "input"))
    )
    (net (code "63") (name "Net-(U1-CH1)") (class "Default")
      (node (ref "C17") (pin "2") (pinfunction "2_2") (pintype "passive"))
      (node (ref "R2") (pin "2") (pinfunction "2_2") (pintype "passive"))
      (node (ref "U1") (pin "2") (pinfunction "CH1_2") (pintype "input"))
    )
    (net (code "64") (name "Net-(U1-CH2)") (class "Default")
      (node (ref "C16") (pin "2") (pinfunction "2_2") (pintype "passive"))
      (node (ref "R3") (pin "2") (pinfunction "2_2") (pintype "passive"))
      (node (ref "U1") (pin "3") (pinfunction "CH2_3") (pintype "input"))
    )
    (net (code "65") (name "Net-(U1-CH3)") (class "Default")
      (node (ref "C15") (pin "2") (pinfunction "2_2") (pintype "passive"))
      (node (ref "R4") (pin "2") (pinfunction "2_2") (pintype "passive"))
      (node (ref "U1") (pin "4") (pinfunction "CH3_4") (pintype "input"))
    )
    (net (code "66") (name "Net-(U1-CH4)") (class "Default")
      (node (ref "C14") (pin "1") (pinfunction "1_1") (pintype "passive"))
      (node (ref "R5") (pin "2") (pinfunction "2_2") (pintype "passive"))
      (node (ref "U1") (pin "5") (pinfunction "CH4_5") (pintype "input"))
    )
    (net (code "67") (name "Net-(U1-CH5)") (class "Default")
      (node (ref "C13") (pin "1") (pinfunction "1_1") (pintype "passive"))
      (node (ref "R6") (pin "2") (pinfunction "2_2") (pintype "passive"))
      (node (ref "U1") (pin "6") (pinfunction "CH5_6") (pintype "input"))
    )
    (net (code "68") (name "Net-(U1-CH6)") (class "Default")
      (node (ref "C12") (pin "1") (pinfunction "1_1") (pintype "passive"))
      (node (ref "R7") (pin "2") (pinfunction "2_2") (pintype "passive"))
      (node (ref "U1") (pin "7") (pinfunction "CH6_7") (pintype "input"))
    )
    (net (code "69") (name "Net-(U1-CH7)") (class "Default")
      (node (ref "C11") (pin "1") (pinfunction "1_1") (pintype "passive"))
      (node (ref "R8") (pin "2") (pinfunction "2_2") (pintype "passive"))
      (node (ref "U1") (pin "8") (pinfunction "CH7_8") (pintype "input"))
    )
    (net (code "70") (name "Net-(U1-VREF)") (class "Default")
      (node (ref "C10") (pin "1") (pinfunction "1_1") (pintype "passive"))
      (node (ref "C9") (pin "1") (pinfunction "1_1") (pintype "passive"))
      (node (ref "R11") (pin "1") (pinfunction "1_1") (pintype "passive"))
      (node (ref "U1") (pin "15") (pinfunction "VREF_15") (pintype "input"))
    )
    (net (code "71") (name "Net-(U2-*LDAC)") (class "Default")
      (node (ref "R16") (pin "2") (pinfunction "2_2") (pintype "passive"))
      (node (ref "U2") (pin "8") (pinfunction "*LDAC_8") (pintype "input"))
    )
    (net (code "72") (name "Net-(U2-VOUTA)") (class "Default")
      (node (ref "C6") (pin "2") (pinfunction "2_2") (pintype "passive"))
      (node (ref "R31") (pin "2") (pinfunction "2_2") (pintype "passive"))
      (node (ref "U2") (pin "14") (pinfunction "VOUTA_14") (pintype "output"))
    )
    (net (code "73") (name "Net-(U2-VOUTB)") (class "Default")
      (node (ref "C7") (pin "1") (pinfunction "1_1") (pintype "passive"))
      (node (ref "R32") (pin "2") (pinfunction "2_2") (pintype "passive"))
      (node (ref "U2") (pin "10") (pinfunction "VOUTB_10") (pintype "output"))
    )
    (net (code "74") (name "Net-(U2-VREFA)") (class "Default")
      (node (ref "C19") (pin "1") (pinfunction "1_1") (pintype "passive"))
      (node (ref "C20") (pin "1") (pinfunction "1_1") (pintype "passive"))
      (node (ref "R13") (pin "1") (pinfunction "1_1") (pintype "passive"))
      (node (ref "U2") (pin "11") (pinfunction "VREFB_11") (pintype "input"))
      (node (ref "U2") (pin "13") (pinfunction "VREFA_13") (pintype "input"))
    )
    (net (code "75") (name "Net-(U3-A0)") (class "Default")
      (node (ref "R19") (pin "1") (pinfunction "1_1") (pintype "passive"))
      (node (ref "U3") (pin "15") (pinfunction "A0_15") (pintype "input"))
    )
    (net (code "76") (name "Net-(U3-A1)") (class "Default")
      (node (ref "R20") (pin "1") (pinfunction "1_1") (pintype "passive"))
      (node (ref "U3") (pin "16") (pinfunction "A1_16") (pintype "input"))
    )
    (net (code "77") (name "Net-(U3-A2)") (class "Default")
      (node (ref "R21") (pin "1") (pinfunction "1_1") (pintype "passive"))
      (node (ref "U3") (pin "17") (pinfunction "A2_17") (pintype "input"))
    )
    (net (code "78") (name "Net-(U3-GPA0)") (class "Default")
      (node (ref "SV3") (pin "3") (pinfunction "3_3") (pintype "passive"))
      (node (ref "U3") (pin "21") (pinfunction "GPA0_21") (pintype "bidirectional"))
    )
    (net (code "79") (name "Net-(U3-GPA1)") (class "Default")
      (node (ref "SV3") (pin "5") (pinfunction "5_5") (pintype "passive"))
      (node (ref "U3") (pin "22") (pinfunction "GPA1_22") (pintype "bidirectional"))
    )
    (net (code "80") (name "Net-(U3-GPA2)") (class "Default")
      (node (ref "SV3") (pin "7") (pinfunction "7_7") (pintype "passive"))
      (node (ref "U3") (pin "23") (pinfunction "GPA2_23") (pintype "bidirectional"))
    )
    (net (code "81") (name "Net-(U3-GPA3)") (class "Default")
      (node (ref "SV3") (pin "9") (pinfunction "9_9") (pintype "passive"))
      (node (ref "U3") (pin "24") (pinfunction "GPA3_24") (pintype "bidirectional"))
    )
    (net (code "82") (name "Net-(U3-GPA4)") (class "Default")
      (node (ref "SV3") (pin "11") (pinfunction "11_11") (pintype "passive"))
      (node (ref "U3") (pin "25") (pinfunction "GPA4_25") (pintype "bidirectional"))
    )
    (net (code "83") (name "Net-(U3-GPA5)") (class "Default")
      (node (ref "SV3") (pin "13") (pinfunction "13_13") (pintype "passive"))
      (node (ref "U3") (pin "26") (pinfunction "GPA5_26") (pintype "bidirectional"))
    )
    (net (code "84") (name "Net-(U3-GPA6)") (class "Default")
      (node (ref "SV3") (pin "15") (pinfunction "15_15") (pintype "passive"))
      (node (ref "U3") (pin "27") (pinfunction "GPA6_27") (pintype "bidirectional"))
    )
    (net (code "85") (name "Net-(U3-GPA7)") (class "Default")
      (node (ref "SV3") (pin "17") (pinfunction "17_17") (pintype "passive"))
      (node (ref "U3") (pin "28") (pinfunction "GPA7_28") (pintype "bidirectional"))
    )
    (net (code "86") (name "Net-(U3-GPB0)") (class "Default")
      (node (ref "SV3") (pin "18") (pinfunction "18_18") (pintype "passive"))
      (node (ref "U3") (pin "1") (pinfunction "GPB0_1") (pintype "bidirectional"))
    )
    (net (code "87") (name "Net-(U3-GPB1)") (class "Default")
      (node (ref "SV3") (pin "16") (pinfunction "16_16") (pintype "passive"))
      (node (ref "U3") (pin "2") (pinfunction "GPB1_2") (pintype "bidirectional"))
    )
    (net (code "88") (name "Net-(U3-GPB2)") (class "Default")
      (node (ref "SV3") (pin "14") (pinfunction "14_14") (pintype "passive"))
      (node (ref "U3") (pin "3") (pinfunction "GPB2_3") (pintype "bidirectional"))
    )
    (net (code "89") (name "Net-(U3-GPB3)") (class "Default")
      (node (ref "SV3") (pin "12") (pinfunction "12_12") (pintype "passive"))
      (node (ref "U3") (pin "4") (pinfunction "GPB3_4") (pintype "bidirectional"))
    )
    (net (code "90") (name "Net-(U3-GPB4)") (class "Default")
      (node (ref "SV3") (pin "10") (pinfunction "10_10") (pintype "passive"))
      (node (ref "U3") (pin "5") (pinfunction "GPB4_5") (pintype "bidirectional"))
    )
    (net (code "91") (name "Net-(U3-GPB5)") (class "Default")
      (node (ref "SV3") (pin "8") (pinfunction "8_8") (pintype "passive"))
      (node (ref "U3") (pin "6") (pinfunction "GPB5_6") (pintype "bidirectional"))
    )
    (net (code "92") (name "Net-(U3-GPB6)") (class "Default")
      (node (ref "SV3") (pin "6") (pinfunction "6_6") (pintype "passive"))
      (node (ref "U3") (pin "7") (pinfunction "GPB6_7") (pintype "bidirectional"))
    )
    (net (code "93") (name "Net-(U3-GPB7)") (class "Default")
      (node (ref "SV3") (pin "4") (pinfunction "4_4") (pintype "passive"))
      (node (ref "U3") (pin "8") (pinfunction "GPB7_8") (pintype "bidirectional"))
    )
    (net (code "94") (name "Net-(U4-R-EXT)") (class "Default")
      (node (ref "R18") (pin "2") (pinfunction "2_2") (pintype "passive"))
      (node (ref "U4") (pin "23") (pinfunction "R-EXT_23") (pintype "input"))
    )
    (net (code "95") (name "Net-(U4-~{OE})") (class "Default")
      (node (ref "R22") (pin "1") (pinfunction "1_1") (pintype "passive"))
      (node (ref "U4") (pin "21") (pinfunction "~{OE}_21") (pintype "input"))
    )
    (net (code "96") (name "Net-(U5-BLANK)") (class "Default")
      (node (ref "R24") (pin "2") (pinfunction "2_2") (pintype "passive"))
      (node (ref "U5") (pin "2") (pinfunction "BLANK_2") (pintype "input"))
    )
    (net (code "97") (name "Net-(U5-IREF)") (class "Default")
      (node (ref "R23") (pin "2") (pinfunction "2_2") (pintype "passive"))
      (node (ref "U5") (pin "27") (pinfunction "IREF_27") (pintype "input"))
    )
    (net (code "98") (name "Net-(U9-E3)") (class "Default")
      (node (ref "R33") (pin "1") (pinfunction "1_1") (pintype "passive"))
      (node (ref "U9") (pin "6") (pinfunction "E3_6") (pintype "bidirectional"))
    )
    (net (code "99") (name "Net-(U9-~{E2})") (class "Default")
      (node (ref "R12") (pin "2") (pinfunction "2_2") (pintype "passive"))
      (node (ref "U9") (pin "5") (pinfunction "~{E2}_5") (pintype "bidirectional"))
    )
    (net (code "100") (name "Net-(U10-B)") (class "Default")
      (node (ref "U10") (pin "4") (pinfunction "B_4") (pintype "bidirectional"))
      (node (ref "X100") (pin "21") (pinfunction "MISO0_21") (pintype "passive"))
    )
    (net (code "101") (name "Net-(U10-~{OE})") (class "Default")
      (node (ref "R30") (pin "2") (pinfunction "2_2") (pintype "passive"))
      (node (ref "U10") (pin "1") (pinfunction "~{OE}_1") (pintype "bidirectional"))
    )
    (net (code "102") (name "Net-(X2C-1)") (class "Default")
      (node (ref "U$2") (pin "8") (pinfunction "OUT2_8") (pintype "output"))
      (node (ref "U$2") (pin "9") (pinfunction "OUT2_9") (pintype "output"))
      (node (ref "X2") (pin "3") (pinfunction "1_3") (pintype "passive"))
    )
    (net (code "103") (name "unconnected-(U$2-STAT1-Pad4)") (class "Default")
      (node (ref "U$2") (pin "4") (pinfunction "STAT1_4") (pintype "output"))
    )
    (net (code "104") (name "unconnected-(U$2-STAT2-Pad5)") (class "Default")
      (node (ref "U$2") (pin "5") (pinfunction "STAT2_5") (pintype "output"))
    )
    (net (code "105") (name "unconnected-(U$2-STAT_D-Pad2)") (class "Default")
      (node (ref "U$2") (pin "2") (pinfunction "STAT_D_2") (pintype "input"))
    )
    (net (code "106") (name "unconnected-(U$3-A2-Pad5)") (class "Default")
      (node (ref "U$3") (pin "5") (pinfunction "A2_5") (pintype "bidirectional"))
    )
    (net (code "107") (name "unconnected-(U2-NC-Pad7)") (class "Default")
      (node (ref "U2") (pin "7") (pinfunction "NC_7") (pintype "no_connect"))
    )
    (net (code "108") (name "unconnected-(U2-NC_2-Pad2)") (class "Default")
      (node (ref "U2") (pin "2") (pinfunction "NC_2_2") (pintype "no_connect"))
    )
    (net (code "109") (name "unconnected-(U2-NC_3-Pad6)") (class "Default")
      (node (ref "U2") (pin "6") (pinfunction "NC_3_6") (pintype "no_connect"))
    )
    (net (code "110") (name "unconnected-(U3-INTA-Pad20)") (class "Default")
      (node (ref "U3") (pin "20") (pinfunction "INTA_20") (pintype "output"))
    )
    (net (code "111") (name "unconnected-(U3-INTB-Pad19)") (class "Default")
      (node (ref "U3") (pin "19") (pinfunction "INTB_19") (pintype "output"))
    )
    (net (code "112") (name "unconnected-(U4-SDO-Pad22)") (class "Default")
      (node (ref "U4") (pin "22") (pinfunction "SDO_22") (pintype "bidirectional"))
    )
    (net (code "113") (name "unconnected-(U5-EP-Pad29)") (class "Default")
      (node (ref "U5") (pin "29") (pinfunction "EP_29") (pintype "passive"))
    )
    (net (code "114") (name "unconnected-(U5-SOUT-Pad24)") (class "Default")
      (node (ref "U5") (pin "24") (pinfunction "SOUT_24") (pintype "output"))
    )
    (net (code "115") (name "unconnected-(U5-XERR-Pad23)") (class "Default")
      (node (ref "U5") (pin "23") (pinfunction "XERR_23") (pintype "output"))
    )
    (net (code "116") (name "unconnected-(U6-CO-Pad5)") (class "Default")
      (node (ref "U6") (pin "5") (pinfunction "CO_5") (pintype "bidirectional"))
    )
    (net (code "117") (name "unconnected-(U6-DO-Pad6)") (class "Default")
      (node (ref "U6") (pin "6") (pinfunction "DO_6") (pintype "bidirectional"))
    )
    (net (code "118") (name "unconnected-(U9-~{Y0}-Pad15)") (class "Default")
      (node (ref "U9") (pin "15") (pinfunction "~{Y0}_15") (pintype "bidirectional"))
    )
    (net (code "119") (name "unconnected-(U9-~{Y4}-Pad11)") (class "Default")
      (node (ref "U9") (pin "11") (pinfunction "~{Y4}_11") (pintype "bidirectional"))
    )
    (net (code "120") (name "unconnected-(U9-~{Y5}-Pad10)") (class "Default")
      (node (ref "U9") (pin "10") (pinfunction "~{Y5}_10") (pintype "bidirectional"))
    )
    (net (code "121") (name "unconnected-(U9-~{Y6}-Pad9)") (class "Default")
      (node (ref "U9") (pin "9") (pinfunction "~{Y6}_9") (pintype "bidirectional"))
    )
    (net (code "122") (name "unconnected-(X100-3V3-Pad1)") (class "Default")
      (node (ref "X100") (pin "1") (pinfunction "3V3_1") (pintype "passive"))
    )
    (net (code "123") (name "unconnected-(X100-CS0_1-Pad26)") (class "Default")
      (node (ref "X100") (pin "26") (pinfunction "CS0_1_26") (pintype "passive"))
    )
    (net (code "124") (name "unconnected-(X100-CS1_0-Pad11)") (class "Default")
      (node (ref "X100") (pin "11") (pinfunction "CS1_0_11") (pintype "passive"))
    )
    (net (code "125") (name "unconnected-(X100-IO5-Pad29)") (class "Default")
      (node (ref "X100") (pin "29") (pinfunction "IO5_29") (pintype "passive"))
    )
    (net (code "126") (name "unconnected-(X100-IO16-Pad36)") (class "Default")
      (node (ref "X100") (pin "36") (pinfunction "IO16_36") (pintype "passive"))
    )
    (net (code "127") (name "unconnected-(X100-IO24-Pad18)") (class "Default")
      (node (ref "X100") (pin "18") (pinfunction "IO24_18") (pintype "passive"))
    )
    (net (code "128") (name "unconnected-(X100-IO25-Pad22)") (class "Default")
      (node (ref "X100") (pin "22") (pinfunction "IO25_22") (pintype "passive"))
    )
    (net (code "129") (name "unconnected-(X100-MISO1-Pad35)") (class "Default")
      (node (ref "X100") (pin "35") (pinfunction "MISO1_35") (pintype "passive"))
    )
    (net (code "130") (name "unconnected-(X100-R8-Pad8)") (class "Default")
      (node (ref "X100") (pin "8") (pinfunction "R8_8") (pintype "passive"))
    )
    (net (code "131") (name "unconnected-(X100-R10-Pad10)") (class "Default")
      (node (ref "X100") (pin "10") (pinfunction "R10_10") (pintype "passive"))
    )
    (net (code "132") (name "unconnected-(X100-R27-Pad27)") (class "Default")
      (node (ref "X100") (pin "27") (pinfunction "R27_27") (pintype "passive"))
    )
    (net (code "133") (name "unconnected-(X100-R28-Pad28)") (class "Default")
      (node (ref "X100") (pin "28") (pinfunction "R28_28") (pintype "passive"))
    )
    (net (code "134") (name "unconnected-(X100-SCL1-Pad5)") (class "Default")
      (node (ref "X100") (pin "5") (pinfunction "SCL1_5") (pintype "passive"))
    )
    (net (code "135") (name "unconnected-(X100-SDA1-Pad3)") (class "Default")
      (node (ref "X100") (pin "3") (pinfunction "SDA1_3") (pintype "passive"))
    )
  )
)
